# VCU-S04-V00-PSU5V-2A.net
KiCad netlist of a schematic drawn in Altium Designer
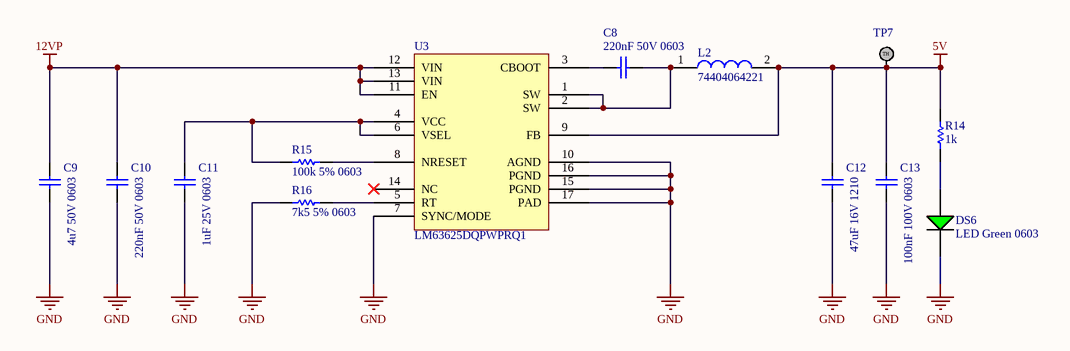
[diagram p0: VCU-S04-V00-PSU5V-2A.SchDoc]

(export (version "E")
  (design (tool "Eeschema 10.0.6"))
  (components
    (comp (ref "C8")
      (value "220nF 50V 0603")
      (footprint "Cap_Ceramic_0603")
      (description "Capacitor, Ceramic, SMD, 220nF, 50V, 5%, X7R, 0603")
      (libsource (lib "StandardCapacitors") (part "220nF 50V 5% X7R 0603"))
    )
    (comp (ref "C9")
      (value "4u7 50V 0603")
      (footprint "Cap_Ceramic_0603")
      (description "Capacitor, Ceramic, SMD, 4u7, 50V, 5%, X7R, 0603")
      (libsource (lib "StandardCapacitors") (part "4u7 50V 5% X7R 0603"))
    )
    (comp (ref "C10")
      (value "220nF 50V 0603")
      (footprint "Cap_Ceramic_0603")
      (description "Capacitor, Ceramic, SMD, 220nF, 50V, 5%, X7R, 0603")
      (libsource (lib "StandardCapacitors") (part "220nF 50V 5% X7R 0603"))
    )
    (comp (ref "C11")
      (value "1uF 25V 0603")
      (footprint "Cap_Ceramic_0603")
      (description "Capacitor, Ceramic, SMD, 1uF, 25V, 5%, X7R, 0603")
      (libsource (lib "StandardCapacitors") (part "1uF 25V 5% X7R 0603"))
    )
    (comp (ref "C12")
      (value "47uF 16V 1210")
      (footprint "Cap_Ceramic_1210")
      (description "Capacitor, Ceramic, SMD, 47uF, 16V, 5%, X7R, 1210")
      (libsource (lib "StandardCapacitors") (part "47uF 16V 10% X7R 1210"))
    )
    (comp (ref "C13")
      (value "100nF 100V 0603")
      (footprint "Cap_Ceramic_0603")
      (description "Capacitor, Ceramic, SMD, 100nF, 100V, 5%, X7R, 0603")
      (libsource (lib "StandardCapacitors") (part "100nF 100V 5% X7R 0603"))
    )
    (comp (ref "DS6")
      (value "LED Green 0603")
      (footprint "LED GREEN 0603")
      (libsource (lib "QUTMS_LEDLibrary") (part "LED Green 0603"))
    )
    (comp (ref "L2")
      (value "74404064221")
      (footprint "Inductor_6x6mm")
      (description "FIXED IND 220UH 660MA 850 MOHM")
      (libsource (lib "QUTMS_InductorLibrary") (part "74404064221"))
    )
    (comp (ref "R14")
      (value "1k")
      (footprint "Res_ThinFilm_0603")
      (description "Resistor, SMD, 1k, 0.1W, 5%, 0603")
      (libsource (lib "StandardResistors") (part "1k 5% 0603"))
    )
    (comp (ref "R15")
      (value "100k 5% 0603")
      (footprint "Res_ThinFilm_0603")
      (description "Resistor, SMD, 100k, 0.1W, 5%, 0603")
      (libsource (lib "StandardResistors") (part "100k 5%, 0603"))
    )
    (comp (ref "R16")
      (value "7k5 5% 0603")
      (footprint "Res_ThinFilm_0603")
      (description "Resistor, SMD, 7k5, 0.1W, 5%, 0603")
      (libsource (lib "StandardResistors") (part "7k5 5% 0603"))
    )
    (comp (ref "TP7")
      (value "TestPoint")
      (footprint "TestPoint")
      (libsource (lib "StandardTest") (part "TestPoint"))
    )
    (comp (ref "U3")
      (value "LM63625DQPWPRQ1")
      (libsource (lib "QUTMS_IntegratedCircuitLibrary") (part "LM63625DQPWPRQ1"))
    )
  )
  (nets
    (net (code "1") (name "5V") (class "Default")
      (node (ref "C12") (pin "2") (pinfunction "2_2") (pintype "passive"))
      (node (ref "C13") (pin "2") (pinfunction "2_2") (pintype "passive"))
      (node (ref "L2") (pin "2") (pinfunction "2_2") (pintype "passive"))
      (node (ref "R14") (pin "2") (pinfunction "2_2") (pintype "passive"))
      (node (ref "TP7") (pin "1") (pinfunction "1_1") (pintype "passive"))
      (node (ref "U3") (pin "9") (pinfunction "FB_9") (pintype "passive"))
    )
    (net (code "2") (name "12VP") (class "Default")
      (node (ref "C10") (pin "2") (pinfunction "2_2") (pintype "passive"))
      (node (ref "C9") (pin "2") (pinfunction "2_2") (pintype "passive"))
      (node (ref "U3") (pin "11") (pinfunction "EN_11") (pintype "passive"))
      (node (ref "U3") (pin "12") (pinfunction "VIN_12") (pintype "passive"))
      (node (ref "U3") (pin "13") (pinfunction "VIN_13") (pintype "passive"))
    )
    (net (code "3") (name "GND") (class "Default")
      (node (ref "C10") (pin "1") (pinfunction "1_1") (pintype "passive"))
      (node (ref "C11") (pin "1") (pinfunction "1_1") (pintype "passive"))
      (node (ref "C12") (pin "1") (pinfunction "1_1") (pintype "passive"))
      (node (ref "C13") (pin "1") (pinfunction "1_1") (pintype "passive"))
      (node (ref "C9") (pin "1") (pinfunction "1_1") (pintype "passive"))
      (node (ref "DS6") (pin "2") (pinfunction "C_2") (pintype "passive"))
      (node (ref "R16") (pin "1") (pinfunction "1_1") (pintype "passive"))
      (node (ref "U3") (pin "10") (pinfunction "AGND_10") (pintype "passive"))
      (node (ref "U3") (pin "15") (pinfunction "PGND_15") (pintype "passive"))
      (node (ref "U3") (pin "16") (pinfunction "PGND_16") (pintype "passive"))
      (node (ref "U3") (pin "17") (pinfunction "PAD_17") (pintype "passive"))
      (node (ref "U3") (pin "7") (pinfunction "SYNC/MODE_7") (pintype "passive"))
    )
    (net (code "4") (name "Net-(C8-Pad2)") (class "Default")
      (node (ref "C8") (pin "2") (pinfunction "2_2") (pintype "passive"))
      (node (ref "L2") (pin "1") (pinfunction "1_1") (pintype "passive"))
      (node (ref "U3") (pin "1") (pinfunction "SW_1") (pintype "passive"))
      (node (ref "U3") (pin "2") (pinfunction "SW_2") (pintype "passive"))
    )
    (net (code "5") (name "Net-(DS6-A)") (class "Default")
      (node (ref "DS6") (pin "1") (pinfunction "A_1") (pintype "passive"))
      (node (ref "R14") (pin "1") (pinfunction "1_1") (pintype "passive"))
    )
    (net (code "6") (name "Net-(U3-CBOOT)") (class "Default")
      (node (ref "C8") (pin "1") (pinfunction "1_1") (pintype "passive"))
      (node (ref "U3") (pin "3") (pinfunction "CBOOT_3") (pintype "passive"))
    )
    (net (code "7") (name "Net-(U3-NRESET)") (class "Default")
      (node (ref "R15") (pin "2") (pinfunction "2_2") (pintype "passive"))
      (node (ref "U3") (pin "8") (pinfunction "NRESET_8") (pintype "passive"))
    )
    (net (code "8") (name "Net-(U3-RT)") (class "Default")
      (node (ref "R16") (pin "2") (pinfunction "2_2") (pintype "passive"))
      (node (ref "U3") (pin "5") (pinfunction "RT_5") (pintype "passive"))
    )
    (net (code "9") (name "Net-(U3-VCC)") (class "Default")
      (node (ref "C11") (pin "2") (pinfunction "2_2") (pintype "passive"))
      (node (ref "R15") (pin "1") (pinfunction "1_1") (pintype "passive"))
      (node (ref "U3") (pin "4") (pinfunction "VCC_4") (pintype "passive"))
      (node (ref "U3") (pin "6") (pinfunction "VSEL_6") (pintype "passive"))
    )
    (net (code "10") (name "unconnected-(U3-NC-Pad14)") (class "Default")
      (node (ref "U3") (pin "14") (pinfunction "NC_14") (pintype "passive+no_connect"))
    )
  )
)
